# shift-in-midi.net
KiCad netlist of a schematic drawn in EAGLE
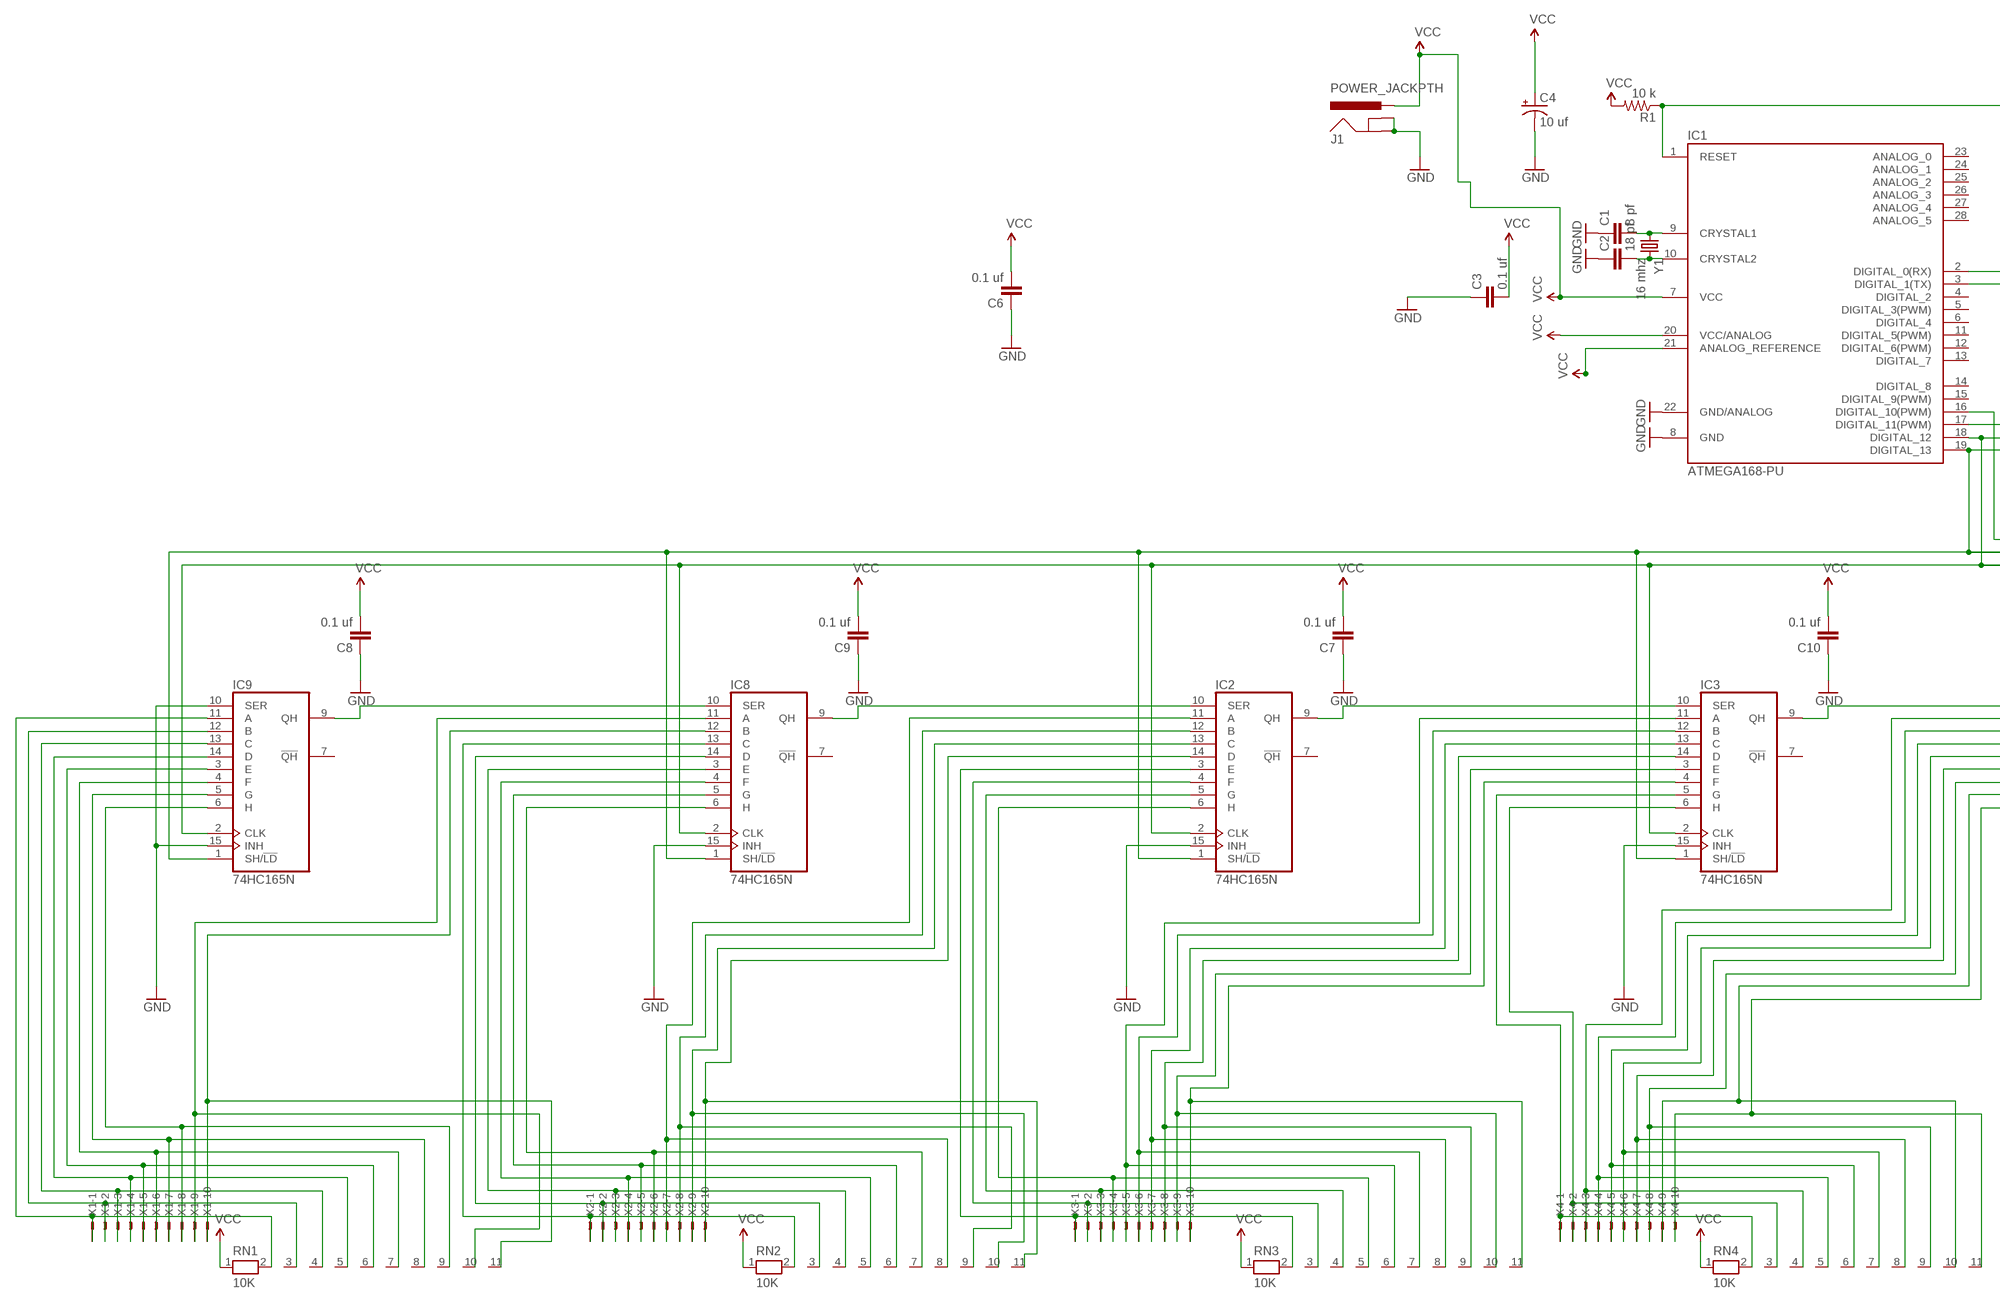
[diagram p0: schematic, sheet 1, part 1 of 2]
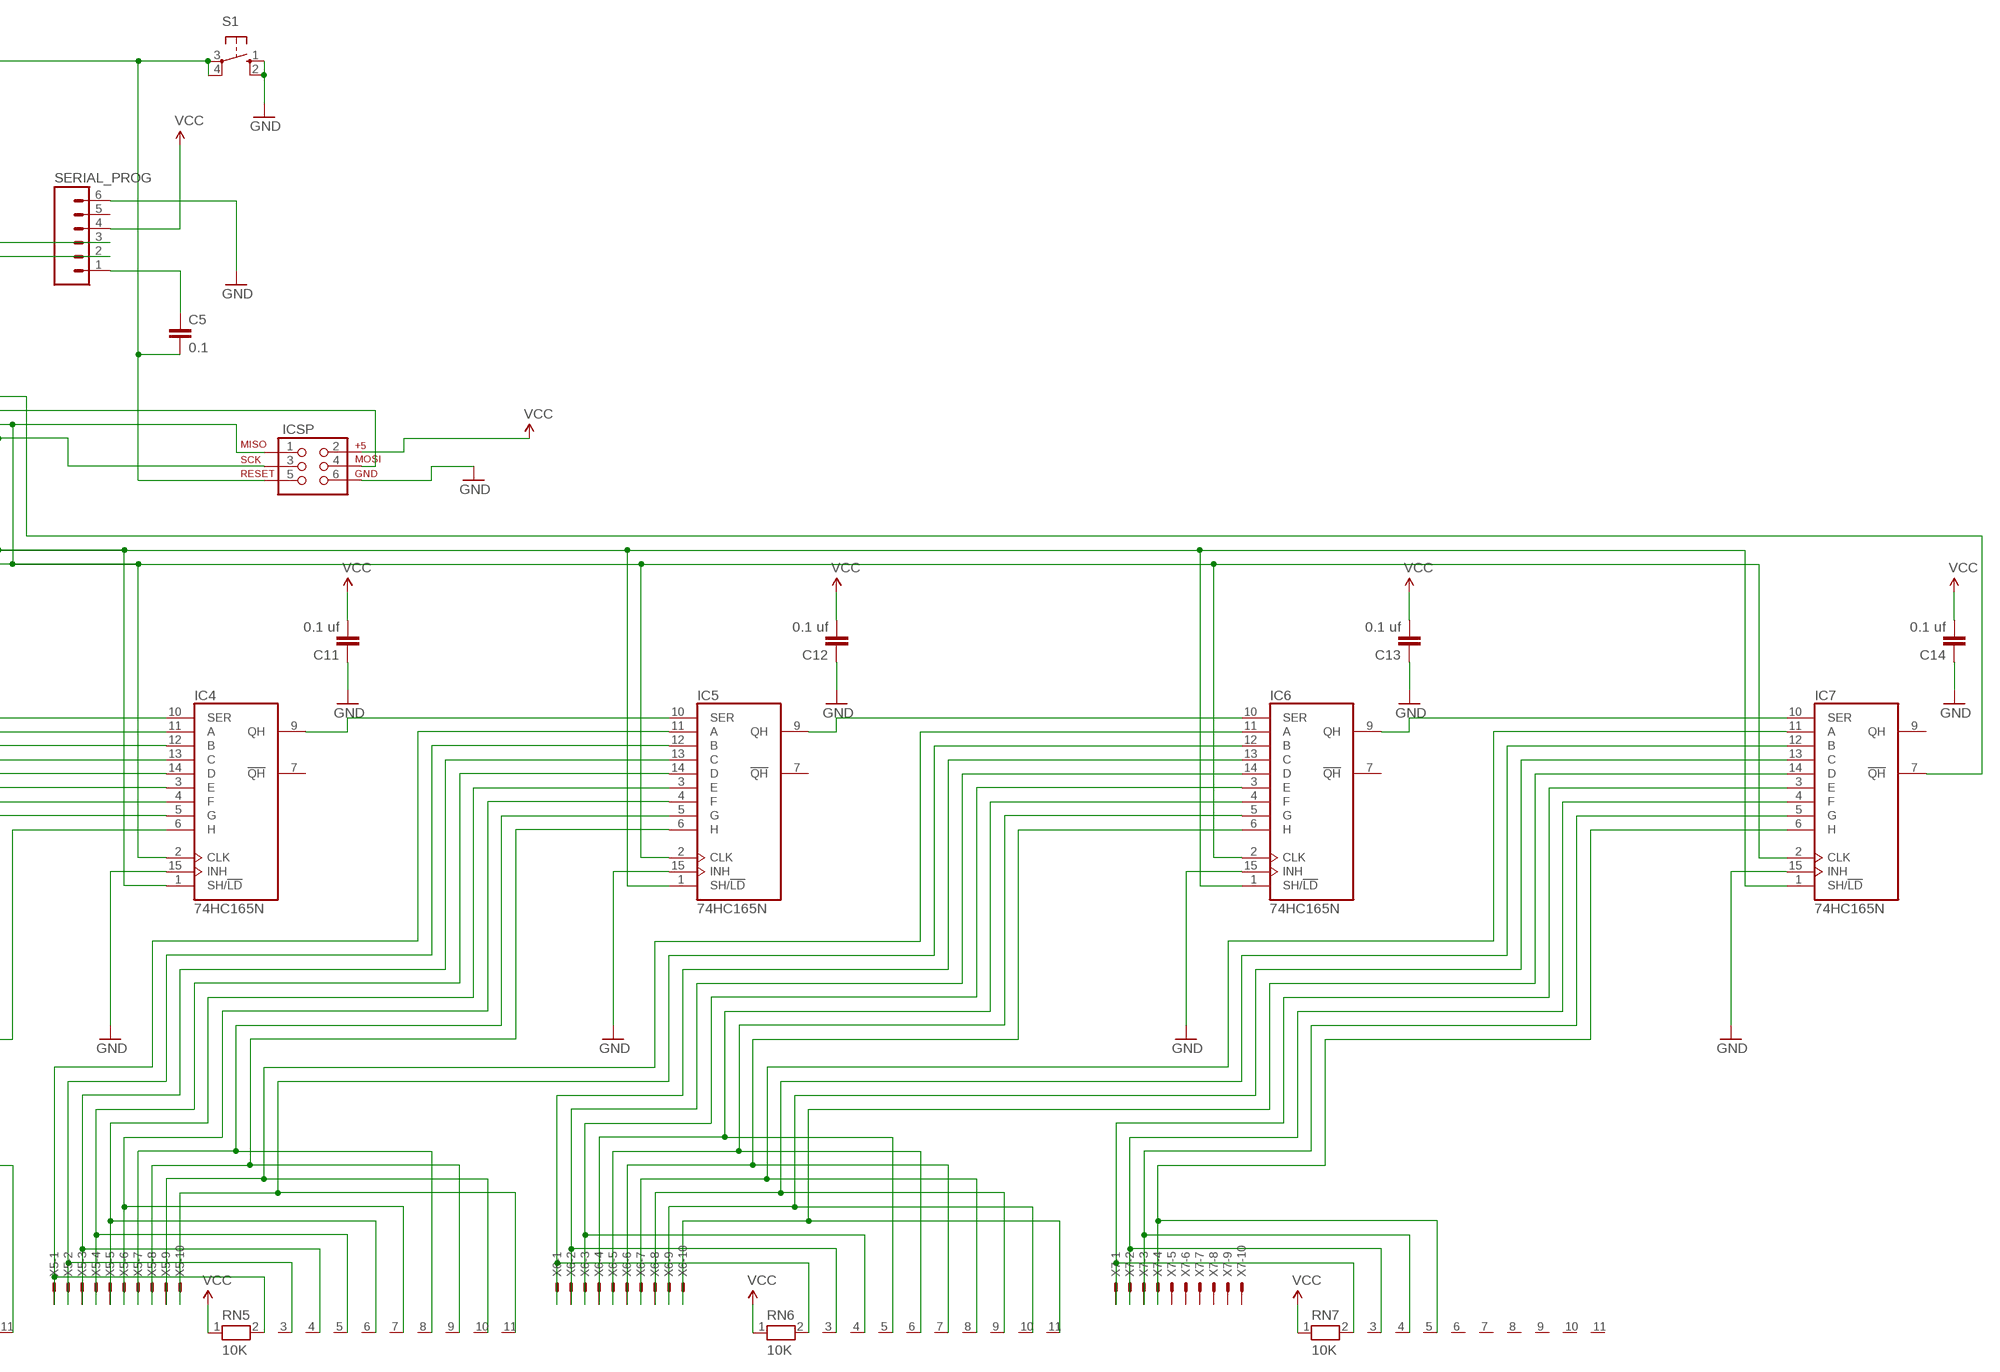
[diagram p1: schematic, sheet 1, part 2 of 2]

(export (version "E")
  (design (tool "Eeschema 10.0.6"))
  (components
    (comp (ref "C1")
      (value "8 pf")
      (footprint "eagle-import:CAP-PTH-SMALL2")
      (libsource (lib "eagle-import") (part "CAPPTH2"))
    )
    (comp (ref "C2")
      (value "18 pf")
      (footprint "eagle-import:CAP-PTH-SMALL2")
      (libsource (lib "eagle-import") (part "CAPPTH2"))
    )
    (comp (ref "C3")
      (value "0.1 uf")
      (footprint "eagle-import:CAP-PTH-SMALL2")
      (libsource (lib "eagle-import") (part "CAPPTH2"))
    )
    (comp (ref "C4")
      (value "10 uf")
      (footprint "eagle-import:CPOL-RADIAL-10UF-25V")
      (libsource (lib "eagle-import") (part "CAP_POLPTH2"))
    )
    (comp (ref "C5")
      (value "0.1")
      (footprint "eagle-import:CAP-PTH-SMALL")
      (libsource (lib "eagle-import") (part "SparkFun-Passives_CAPPTH"))
    )
    (comp (ref "C6")
      (value "0.1 uf")
      (footprint "eagle-import:CAP-PTH-SMALL2")
      (libsource (lib "eagle-import") (part "CAPPTH2"))
    )
    (comp (ref "C7")
      (value "0.1 uf")
      (footprint "eagle-import:CAP-PTH-SMALL2")
      (libsource (lib "eagle-import") (part "CAPPTH2"))
    )
    (comp (ref "C8")
      (value "0.1 uf")
      (footprint "eagle-import:CAP-PTH-SMALL2")
      (libsource (lib "eagle-import") (part "CAPPTH2"))
    )
    (comp (ref "C9")
      (value "0.1 uf")
      (footprint "eagle-import:CAP-PTH-SMALL2")
      (libsource (lib "eagle-import") (part "CAPPTH2"))
    )
    (comp (ref "C10")
      (value "0.1 uf")
      (footprint "eagle-import:CAP-PTH-SMALL2")
      (libsource (lib "eagle-import") (part "CAPPTH2"))
    )
    (comp (ref "C11")
      (value "0.1 uf")
      (footprint "eagle-import:CAP-PTH-SMALL2")
      (libsource (lib "eagle-import") (part "CAPPTH2"))
    )
    (comp (ref "C12")
      (value "0.1 uf")
      (footprint "eagle-import:CAP-PTH-SMALL2")
      (libsource (lib "eagle-import") (part "CAPPTH2"))
    )
    (comp (ref "C13")
      (value "0.1 uf")
      (footprint "eagle-import:CAP-PTH-SMALL2")
      (libsource (lib "eagle-import") (part "CAPPTH2"))
    )
    (comp (ref "C14")
      (value "0.1 uf")
      (footprint "eagle-import:CAP-PTH-SMALL2")
      (libsource (lib "eagle-import") (part "CAPPTH2"))
    )
    (comp (ref "IC1")
      (value "ATMEGA168-PU")
      (footprint "eagle-import:DIL28-3")
      (libsource (lib "eagle-import") (part "ATMEGA168-PU"))
    )
    (comp (ref "IC2")
      (value "74HC165N")
      (footprint "eagle-import:DIL16")
      (libsource (lib "eagle-import") (part "74165NHC"))
    )
    (comp (ref "IC3")
      (value "74HC165N")
      (footprint "eagle-import:DIL16")
      (libsource (lib "eagle-import") (part "74165NHC"))
    )
    (comp (ref "IC4")
      (value "74HC165N")
      (footprint "eagle-import:DIL16")
      (libsource (lib "eagle-import") (part "74165NHC"))
    )
    (comp (ref "IC5")
      (value "74HC165N")
      (footprint "eagle-import:DIL16")
      (libsource (lib "eagle-import") (part "74165NHC"))
    )
    (comp (ref "IC6")
      (value "74HC165N")
      (footprint "eagle-import:DIL16")
      (libsource (lib "eagle-import") (part "74165NHC"))
    )
    (comp (ref "IC7")
      (value "74HC165N")
      (footprint "eagle-import:DIL16")
      (libsource (lib "eagle-import") (part "74165NHC"))
    )
    (comp (ref "IC8")
      (value "74HC165N")
      (footprint "eagle-import:DIL16")
      (libsource (lib "eagle-import") (part "74165NHC"))
    )
    (comp (ref "IC9")
      (value "74HC165N")
      (footprint "eagle-import:DIL16")
      (libsource (lib "eagle-import") (part "74165NHC"))
    )
    (comp (ref "ICSP")
      (value "AVR_SPI_PRG_62X3_LOCK")
      (footprint "eagle-import:2X3_LOCK")
      (libsource (lib "eagle-import") (part "AVR_SPI_PRG_62X3_LOCK"))
    )
    (comp (ref "J1")
      (value "POWER_JACKPTH")
      (footprint "eagle-import:POWER_JACK_PTH")
      (libsource (lib "eagle-import") (part "POWER_JACKPTH"))
    )
    (comp (ref "R1")
      (value "10 k")
      (footprint "eagle-import:AXIAL-0.4")
      (libsource (lib "eagle-import") (part "RESISTORPTH-1/4W"))
    )
    (comp (ref "RN1")
      (value "10K")
      (footprint "eagle-import:RN-11")
      (libsource (lib "eagle-import") (part "RN10"))
    )
    (comp (ref "RN2")
      (value "10K")
      (footprint "eagle-import:RN-11")
      (fields (field (name "OC_FARNELL") "unknown") (field (name "OC_NEWARK") "unknown"))
      (libsource (lib "eagle-import") (part "RN10"))
    )
    (comp (ref "RN3")
      (value "10K")
      (footprint "eagle-import:RN-11")
      (fields (field (name "OC_FARNELL") "unknown") (field (name "OC_NEWARK") "unknown"))
      (libsource (lib "eagle-import") (part "RN10"))
    )
    (comp (ref "RN4")
      (value "10K")
      (footprint "eagle-import:RN-11")
      (fields (field (name "OC_FARNELL") "unknown") (field (name "OC_NEWARK") "unknown"))
      (libsource (lib "eagle-import") (part "RN10"))
    )
    (comp (ref "RN5")
      (value "10K")
      (footprint "eagle-import:RN-11")
      (fields (field (name "OC_FARNELL") "unknown") (field (name "OC_NEWARK") "unknown"))
      (libsource (lib "eagle-import") (part "RN10"))
    )
    (comp (ref "RN6")
      (value "10K")
      (footprint "eagle-import:RN-11")
      (fields (field (name "OC_FARNELL") "unknown") (field (name "OC_NEWARK") "unknown"))
      (libsource (lib "eagle-import") (part "RN10"))
    )
    (comp (ref "RN7")
      (value "10K")
      (footprint "eagle-import:RN-11")
      (fields (field (name "OC_FARNELL") "unknown") (field (name "OC_NEWARK") "unknown"))
      (libsource (lib "eagle-import") (part "RN10"))
    )
    (comp (ref "S1")
      (value "10-XX")
      (footprint "eagle-import:B3F-10XX")
      (fields (field (name "MPN") "B3F-1000"))
      (libsource (lib "eagle-import") (part "10-XX"))
    )
    (comp (ref "SERIAL_PROG")
      (value "M06LONGPADS")
      (footprint "eagle-import:1X06_LONGPADS")
      (libsource (lib "eagle-import") (part "M06LONGPADS"))
    )
    (comp (ref "X1")
      (value "KK-156-10")
      (footprint "eagle-import:KK-156-10")
      (libsource (lib "eagle-import") (part "KK-156-10"))
    )
    (comp (ref "X2")
      (value "KK-156-10")
      (footprint "eagle-import:KK-156-10")
      (libsource (lib "eagle-import") (part "KK-156-10"))
    )
    (comp (ref "X3")
      (value "KK-156-10")
      (footprint "eagle-import:KK-156-10")
      (libsource (lib "eagle-import") (part "KK-156-10"))
    )
    (comp (ref "X4")
      (value "KK-156-10")
      (footprint "eagle-import:KK-156-10")
      (libsource (lib "eagle-import") (part "KK-156-10"))
    )
    (comp (ref "X5")
      (value "KK-156-10")
      (footprint "eagle-import:KK-156-10")
      (libsource (lib "eagle-import") (part "KK-156-10"))
    )
    (comp (ref "X6")
      (value "KK-156-10")
      (footprint "eagle-import:KK-156-10")
      (libsource (lib "eagle-import") (part "KK-156-10"))
    )
    (comp (ref "X7")
      (value "KK-156-10")
      (footprint "eagle-import:KK-156-10")
      (libsource (lib "eagle-import") (part "KK-156-10"))
    )
    (comp (ref "Y1")
      (value "16 mhz")
      (footprint "eagle-import:HC49US")
      (libsource (lib "eagle-import") (part "CRYSTALHC49US"))
    )
  )
  (nets
    (net (code "1") (name "GND") (class "Default")
      (node (ref "C1") (pin "1") (pinfunction "1_1") (pintype "passive"))
      (node (ref "C10") (pin "1") (pinfunction "1_1") (pintype "passive"))
      (node (ref "C11") (pin "1") (pinfunction "1_1") (pintype "passive"))
      (node (ref "C12") (pin "1") (pinfunction "1_1") (pintype "passive"))
      (node (ref "C13") (pin "1") (pinfunction "1_1") (pintype "passive"))
      (node (ref "C14") (pin "1") (pinfunction "1_1") (pintype "passive"))
      (node (ref "C2") (pin "1") (pinfunction "1_1") (pintype "passive"))
      (node (ref "C3") (pin "1") (pinfunction "1_1") (pintype "passive"))
      (node (ref "C4") (pin "2") (pinfunction "-_2") (pintype "passive"))
      (node (ref "C6") (pin "1") (pinfunction "1_1") (pintype "passive"))
      (node (ref "C7") (pin "1") (pinfunction "1_1") (pintype "passive"))
      (node (ref "C8") (pin "1") (pinfunction "1_1") (pintype "passive"))
      (node (ref "C9") (pin "1") (pinfunction "1_1") (pintype "passive"))
      (node (ref "IC1") (pin "22") (pinfunction "GND/ANALOG_22") (pintype "power_in"))
      (node (ref "IC1") (pin "8") (pinfunction "GND_8") (pintype "power_in"))
      (node (ref "IC2") (pin "15") (pinfunction "INH_15") (pintype "input"))
      (node (ref "IC3") (pin "15") (pinfunction "INH_15") (pintype "input"))
      (node (ref "IC4") (pin "15") (pinfunction "INH_15") (pintype "input"))
      (node (ref "IC5") (pin "15") (pinfunction "INH_15") (pintype "input"))
      (node (ref "IC6") (pin "15") (pinfunction "INH_15") (pintype "input"))
      (node (ref "IC7") (pin "15") (pinfunction "INH_15") (pintype "input"))
      (node (ref "IC8") (pin "15") (pinfunction "INH_15") (pintype "input"))
      (node (ref "IC9") (pin "10") (pinfunction "SER_10") (pintype "input"))
      (node (ref "IC9") (pin "15") (pinfunction "INH_15") (pintype "input"))
      (node (ref "ICSP") (pin "6") (pinfunction "6_6") (pintype "passive"))
      (node (ref "J1") (pin "GND") (pinfunction "GND_GND") (pintype "bidirectional"))
      (node (ref "J1") (pin "GNDBREAK") (pinfunction "GNDBREAK_GNDBREAK") (pintype "bidirectional"))
      (node (ref "S1") (pin "1") (pinfunction "S_1") (pintype "passive"))
      (node (ref "S1") (pin "2") (pinfunction "S1_2") (pintype "passive"))
      (node (ref "SERIAL_PROG") (pin "6") (pinfunction "6_6") (pintype "passive"))
    )
    (net (code "2") (name "Net-(C5-Pad1)") (class "Default")
      (node (ref "C5") (pin "1") (pinfunction "1_1") (pintype "passive"))
      (node (ref "SERIAL_PROG") (pin "1") (pinfunction "1_1") (pintype "passive"))
    )
    (net (code "3") (name "Net-(IC1-CRYSTAL1)") (class "Default")
      (node (ref "C1") (pin "2") (pinfunction "2_2") (pintype "passive"))
      (node (ref "IC1") (pin "9") (pinfunction "CRYSTAL1_9") (pintype "bidirectional"))
      (node (ref "Y1") (pin "1") (pinfunction "1_1") (pintype "passive"))
    )
    (net (code "4") (name "Net-(IC1-CRYSTAL2)") (class "Default")
      (node (ref "C2") (pin "2") (pinfunction "2_2") (pintype "passive"))
      (node (ref "IC1") (pin "10") (pinfunction "CRYSTAL2_10") (pintype "bidirectional"))
      (node (ref "Y1") (pin "2") (pinfunction "2_2") (pintype "passive"))
    )
    (net (code "5") (name "Net-(IC1-DIGITAL_0(RX))") (class "Default")
      (node (ref "IC1") (pin "2") (pinfunction "DIGITAL_0(RX)_2") (pintype "bidirectional"))
      (node (ref "SERIAL_PROG") (pin "3") (pinfunction "3_3") (pintype "passive"))
    )
    (net (code "6") (name "Net-(IC1-DIGITAL_1(TX))") (class "Default")
      (node (ref "IC1") (pin "3") (pinfunction "DIGITAL_1(TX)_3") (pintype "bidirectional"))
      (node (ref "SERIAL_PROG") (pin "2") (pinfunction "2_2") (pintype "passive"))
    )
    (net (code "7") (name "Net-(IC1-DIGITAL_10(PWM))") (class "Default")
      (node (ref "IC1") (pin "16") (pinfunction "DIGITAL_10(PWM)_16") (pintype "bidirectional"))
      (node (ref "IC7") (pin "7") (pinfunction "~{QH}_7") (pintype "output"))
    )
    (net (code "8") (name "Net-(IC1-DIGITAL_11(PWM))") (class "Default")
      (node (ref "IC1") (pin "17") (pinfunction "DIGITAL_11(PWM)_17") (pintype "bidirectional"))
      (node (ref "ICSP") (pin "4") (pinfunction "4_4") (pintype "passive"))
    )
    (net (code "9") (name "Net-(IC1-DIGITAL_12)") (class "Default")
      (node (ref "IC1") (pin "18") (pinfunction "DIGITAL_12_18") (pintype "bidirectional"))
      (node (ref "IC2") (pin "2") (pinfunction "CLK_2") (pintype "input"))
      (node (ref "IC3") (pin "2") (pinfunction "CLK_2") (pintype "input"))
      (node (ref "IC4") (pin "2") (pinfunction "CLK_2") (pintype "input"))
      (node (ref "IC5") (pin "2") (pinfunction "CLK_2") (pintype "input"))
      (node (ref "IC6") (pin "2") (pinfunction "CLK_2") (pintype "input"))
      (node (ref "IC7") (pin "2") (pinfunction "CLK_2") (pintype "input"))
      (node (ref "IC8") (pin "2") (pinfunction "CLK_2") (pintype "input"))
      (node (ref "IC9") (pin "2") (pinfunction "CLK_2") (pintype "input"))
      (node (ref "ICSP") (pin "1") (pinfunction "1_1") (pintype "passive"))
    )
    (net (code "10") (name "Net-(IC1-DIGITAL_13)") (class "Default")
      (node (ref "IC1") (pin "19") (pinfunction "DIGITAL_13_19") (pintype "bidirectional"))
      (node (ref "IC2") (pin "1") (pinfunction "SH/~{LD}_1") (pintype "input"))
      (node (ref "IC3") (pin "1") (pinfunction "SH/~{LD}_1") (pintype "input"))
      (node (ref "IC4") (pin "1") (pinfunction "SH/~{LD}_1") (pintype "input"))
      (node (ref "IC5") (pin "1") (pinfunction "SH/~{LD}_1") (pintype "input"))
      (node (ref "IC6") (pin "1") (pinfunction "SH/~{LD}_1") (pintype "input"))
      (node (ref "IC7") (pin "1") (pinfunction "SH/~{LD}_1") (pintype "input"))
      (node (ref "IC8") (pin "1") (pinfunction "SH/~{LD}_1") (pintype "input"))
      (node (ref "IC9") (pin "1") (pinfunction "SH/~{LD}_1") (pintype "input"))
      (node (ref "ICSP") (pin "3") (pinfunction "3_3") (pintype "passive"))
    )
    (net (code "11") (name "Net-(IC1-RESET)") (class "Default")
      (node (ref "C5") (pin "2") (pinfunction "2_2") (pintype "passive"))
      (node (ref "IC1") (pin "1") (pinfunction "RESET_1") (pintype "bidirectional"))
      (node (ref "ICSP") (pin "5") (pinfunction "5_5") (pintype "passive"))
      (node (ref "R1") (pin "P$1") (pinfunction "1_P$1") (pintype "passive"))
      (node (ref "S1") (pin "3") (pinfunction "P_3") (pintype "passive"))
      (node (ref "S1") (pin "4") (pinfunction "P1_4") (pintype "passive"))
    )
    (net (code "12") (name "Net-(IC2A-A)") (class "Default")
      (node (ref "IC2") (pin "11") (pinfunction "A_11") (pintype "input"))
      (node (ref "RN2") (pin "8") (pinfunction "8_8") (pintype "passive"))
      (node (ref "X2") (pin "7") (pinfunction "S_7") (pintype "passive"))
    )
    (net (code "13") (name "Net-(IC2A-B)") (class "Default")
      (node (ref "IC2") (pin "12") (pinfunction "B_12") (pintype "input"))
      (node (ref "RN2") (pin "9") (pinfunction "9_9") (pintype "passive"))
      (node (ref "X2") (pin "8") (pinfunction "S_8") (pintype "passive"))
    )
    (net (code "14") (name "Net-(IC2A-C)") (class "Default")
      (node (ref "IC2") (pin "13") (pinfunction "C_13") (pintype "input"))
      (node (ref "RN2") (pin "10") (pinfunction "10_10") (pintype "passive"))
      (node (ref "X2") (pin "9") (pinfunction "S_9") (pintype "passive"))
    )
    (net (code "15") (name "Net-(IC2A-D)") (class "Default")
      (node (ref "IC2") (pin "14") (pinfunction "D_14") (pintype "input"))
      (node (ref "RN2") (pin "11") (pinfunction "11_11") (pintype "passive"))
      (node (ref "X2") (pin "10") (pinfunction "S_10") (pintype "passive"))
    )
    (net (code "16") (name "Net-(IC2A-E)") (class "Default")
      (node (ref "IC2") (pin "3") (pinfunction "E_3") (pintype "input"))
      (node (ref "RN3") (pin "2") (pinfunction "2_2") (pintype "passive"))
      (node (ref "X3") (pin "1") (pinfunction "S_1") (pintype "passive"))
    )
    (net (code "17") (name "Net-(IC2A-F)") (class "Default")
      (node (ref "IC2") (pin "4") (pinfunction "F_4") (pintype "input"))
      (node (ref "RN3") (pin "3") (pinfunction "3_3") (pintype "passive"))
      (node (ref "X3") (pin "2") (pinfunction "S_2") (pintype "passive"))
    )
    (net (code "18") (name "Net-(IC2A-G)") (class "Default")
      (node (ref "IC2") (pin "5") (pinfunction "G_5") (pintype "input"))
      (node (ref "RN3") (pin "4") (pinfunction "4_4") (pintype "passive"))
      (node (ref "X3") (pin "3") (pinfunction "S_3") (pintype "passive"))
    )
    (net (code "19") (name "Net-(IC2A-H)") (class "Default")
      (node (ref "IC2") (pin "6") (pinfunction "H_6") (pintype "input"))
      (node (ref "RN3") (pin "5") (pinfunction "5_5") (pintype "passive"))
      (node (ref "X3") (pin "4") (pinfunction "S_4") (pintype "passive"))
    )
    (net (code "20") (name "Net-(IC2A-QH)") (class "Default")
      (node (ref "IC2") (pin "9") (pinfunction "QH_9") (pintype "output"))
      (node (ref "IC3") (pin "10") (pinfunction "SER_10") (pintype "input"))
    )
    (net (code "21") (name "Net-(IC2A-SER)") (class "Default")
      (node (ref "IC2") (pin "10") (pinfunction "SER_10") (pintype "input"))
      (node (ref "IC8") (pin "9") (pinfunction "QH_9") (pintype "output"))
    )
    (net (code "22") (name "Net-(IC3A-A)") (class "Default")
      (node (ref "IC3") (pin "11") (pinfunction "A_11") (pintype "input"))
      (node (ref "RN3") (pin "6") (pinfunction "6_6") (pintype "passive"))
      (node (ref "X3") (pin "5") (pinfunction "S_5") (pintype "passive"))
    )
    (net (code "23") (name "Net-(IC3A-B)") (class "Default")
      (node (ref "IC3") (pin "12") (pinfunction "B_12") (pintype "input"))
      (node (ref "RN3") (pin "7") (pinfunction "7_7") (pintype "passive"))
      (node (ref "X3") (pin "6") (pinfunction "S_6") (pintype "passive"))
    )
    (net (code "24") (name "Net-(IC3A-C)") (class "Default")
      (node (ref "IC3") (pin "13") (pinfunction "C_13") (pintype "input"))
      (node (ref "RN3") (pin "8") (pinfunction "8_8") (pintype "passive"))
      (node (ref "X3") (pin "7") (pinfunction "S_7") (pintype "passive"))
    )
    (net (code "25") (name "Net-(IC3A-D)") (class "Default")
      (node (ref "IC3") (pin "14") (pinfunction "D_14") (pintype "input"))
      (node (ref "RN3") (pin "9") (pinfunction "9_9") (pintype "passive"))
      (node (ref "X3") (pin "8") (pinfunction "S_8") (pintype "passive"))
    )
    (net (code "26") (name "Net-(IC3A-E)") (class "Default")
      (node (ref "IC3") (pin "3") (pinfunction "E_3") (pintype "input"))
      (node (ref "RN3") (pin "10") (pinfunction "10_10") (pintype "passive"))
      (node (ref "X3") (pin "9") (pinfunction "S_9") (pintype "passive"))
    )
    (net (code "27") (name "Net-(IC3A-F)") (class "Default")
      (node (ref "IC3") (pin "4") (pinfunction "F_4") (pintype "input"))
      (node (ref "RN3") (pin "11") (pinfunction "11_11") (pintype "passive"))
      (node (ref "X3") (pin "10") (pinfunction "S_10") (pintype "passive"))
    )
    (net (code "28") (name "Net-(IC3A-G)") (class "Default")
      (node (ref "IC3") (pin "5") (pinfunction "G_5") (pintype "input"))
      (node (ref "RN4") (pin "2") (pinfunction "2_2") (pintype "passive"))
      (node (ref "X4") (pin "1") (pinfunction "S_1") (pintype "passive"))
    )
    (net (code "29") (name "Net-(IC3A-H)") (class "Default")
      (node (ref "IC3") (pin "6") (pinfunction "H_6") (pintype "input"))
      (node (ref "RN4") (pin "3") (pinfunction "3_3") (pintype "passive"))
      (node (ref "X4") (pin "2") (pinfunction "S_2") (pintype "passive"))
    )
    (net (code "30") (name "Net-(IC3A-QH)") (class "Default")
      (node (ref "IC3") (pin "9") (pinfunction "QH_9") (pintype "output"))
      (node (ref "IC4") (pin "10") (pinfunction "SER_10") (pintype "input"))
    )
    (net (code "31") (name "Net-(IC4A-A)") (class "Default")
      (node (ref "IC4") (pin "11") (pinfunction "A_11") (pintype "input"))
      (node (ref "RN4") (pin "4") (pinfunction "4_4") (pintype "passive"))
      (node (ref "X4") (pin "3") (pinfunction "S_3") (pintype "passive"))
    )
    (net (code "32") (name "Net-(IC4A-B)") (class "Default")
      (node (ref "IC4") (pin "12") (pinfunction "B_12") (pintype "input"))
      (node (ref "RN4") (pin "5") (pinfunction "5_5") (pintype "passive"))
      (node (ref "X4") (pin "4") (pinfunction "S_4") (pintype "passive"))
    )
    (net (code "33") (name "Net-(IC4A-C)") (class "Default")
      (node (ref "IC4") (pin "13") (pinfunction "C_13") (pintype "input"))
      (node (ref "RN4") (pin "6") (pinfunction "6_6") (pintype "passive"))
      (node (ref "X4") (pin "5") (pinfunction "S_5") (pintype "passive"))
    )
    (net (code "34") (name "Net-(IC4A-D)") (class "Default")
      (node (ref "IC4") (pin "14") (pinfunction "D_14") (pintype "input"))
      (node (ref "RN4") (pin "7") (pinfunction "7_7") (pintype "passive"))
      (node (ref "X4") (pin "6") (pinfunction "S_6") (pintype "passive"))
    )
    (net (code "35") (name "Net-(IC4A-E)") (class "Default")
      (node (ref "IC4") (pin "3") (pinfunction "E_3") (pintype "input"))
      (node (ref "RN4") (pin "8") (pinfunction "8_8") (pintype "passive"))
      (node (ref "X4") (pin "7") (pinfunction "S_7") (pintype "passive"))
    )
    (net (code "36") (name "Net-(IC4A-F)") (class "Default")
      (node (ref "IC4") (pin "4") (pinfunction "F_4") (pintype "input"))
      (node (ref "RN4") (pin "9") (pinfunction "9_9") (pintype "passive"))
      (node (ref "X4") (pin "8") (pinfunction "S_8") (pintype "passive"))
    )
    (net (code "37") (name "Net-(IC4A-G)") (class "Default")
      (node (ref "IC4") (pin "5") (pinfunction "G_5") (pintype "input"))
      (node (ref "RN4") (pin "10") (pinfunction "10_10") (pintype "passive"))
      (node (ref "X4") (pin "9") (pinfunction "S_9") (pintype "passive"))
    )
    (net (code "38") (name "Net-(IC4A-H)") (class "Default")
      (node (ref "IC4") (pin "6") (pinfunction "H_6") (pintype "input"))
      (node (ref "RN4") (pin "11") (pinfunction "11_11") (pintype "passive"))
      (node (ref "X4") (pin "10") (pinfunction "S_10") (pintype "passive"))
    )
    (net (code "39") (name "Net-(IC4A-QH)") (class "Default")
      (node (ref "IC4") (pin "9") (pinfunction "QH_9") (pintype "output"))
      (node (ref "IC5") (pin "10") (pinfunction "SER_10") (pintype "input"))
    )
    (net (code "40") (name "Net-(IC5A-A)") (class "Default")
      (node (ref "IC5") (pin "11") (pinfunction "A_11") (pintype "input"))
      (node (ref "RN5") (pin "2") (pinfunction "2_2") (pintype "passive"))
      (node (ref "X5") (pin "1") (pinfunction "S_1") (pintype "passive"))
    )
    (net (code "41") (name "Net-(IC5A-B)") (class "Default")
      (node (ref "IC5") (pin "12") (pinfunction "B_12") (pintype "input"))
      (node (ref "RN5") (pin "3") (pinfunction "3_3") (pintype "passive"))
      (node (ref "X5") (pin "2") (pinfunction "S_2") (pintype "passive"))
    )
    (net (code "42") (name "Net-(IC5A-C)") (class "Default")
      (node (ref "IC5") (pin "13") (pinfunction "C_13") (pintype "input"))
      (node (ref "RN5") (pin "4") (pinfunction "4_4") (pintype "passive"))
      (node (ref "X5") (pin "3") (pinfunction "S_3") (pintype "passive"))
    )
    (net (code "43") (name "Net-(IC5A-D)") (class "Default")
      (node (ref "IC5") (pin "14") (pinfunction "D_14") (pintype "input"))
      (node (ref "RN5") (pin "5") (pinfunction "5_5") (pintype "passive"))
      (node (ref "X5") (pin "4") (pinfunction "S_4") (pintype "passive"))
    )
    (net (code "44") (name "Net-(IC5A-E)") (class "Default")
      (node (ref "IC5") (pin "3") (pinfunction "E_3") (pintype "input"))
      (node (ref "RN5") (pin "6") (pinfunction "6_6") (pintype "passive"))
      (node (ref "X5") (pin "5") (pinfunction "S_5") (pintype "passive"))
    )
    (net (code "45") (name "Net-(IC5A-F)") (class "Default")
      (node (ref "IC5") (pin "4") (pinfunction "F_4") (pintype "input"))
      (node (ref "RN5") (pin "7") (pinfunction "7_7") (pintype "passive"))
      (node (ref "X5") (pin "6") (pinfunction "S_6") (pintype "passive"))
    )
    (net (code "46") (name "Net-(IC5A-G)") (class "Default")
      (node (ref "IC5") (pin "5") (pinfunction "G_5") (pintype "input"))
      (node (ref "RN5") (pin "8") (pinfunction "8_8") (pintype "passive"))
      (node (ref "X5") (pin "7") (pinfunction "S_7") (pintype "passive"))
    )
    (net (code "47") (name "Net-(IC5A-H)") (class "Default")
      (node (ref "IC5") (pin "6") (pinfunction "H_6") (pintype "input"))
      (node (ref "RN5") (pin "9") (pinfunction "9_9") (pintype "passive"))
      (node (ref "X5") (pin "8") (pinfunction "S_8") (pintype "passive"))
    )
    (net (code "48") (name "Net-(IC5A-QH)") (class "Default")
      (node (ref "IC5") (pin "9") (pinfunction "QH_9") (pintype "output"))
      (node (ref "IC6") (pin "10") (pinfunction "SER_10") (pintype "input"))
    )
    (net (code "49") (name "Net-(IC6A-A)") (class "Default")
      (node (ref "IC6") (pin "11") (pinfunction "A_11") (pintype "input"))
      (node (ref "RN5") (pin "10") (pinfunction "10_10") (pintype "passive"))
      (node (ref "X5") (pin "9") (pinfunction "S_9") (pintype "passive"))
    )
    (net (code "50") (name "Net-(IC6A-B)") (class "Default")
      (node (ref "IC6") (pin "12") (pinfunction "B_12") (pintype "input"))
      (node (ref "RN5") (pin "11") (pinfunction "11_11") (pintype "passive"))
      (node (ref "X5") (pin "10") (pinfunction "S_10") (pintype "passive"))
    )
    (net (code "51") (name "Net-(IC6A-C)") (class "Default")
      (node (ref "IC6") (pin "13") (pinfunction "C_13") (pintype "input"))
      (node (ref "RN6") (pin "2") (pinfunction "2_2") (pintype "passive"))
      (node (ref "X6") (pin "1") (pinfunction "S_1") (pintype "passive"))
    )
    (net (code "52") (name "Net-(IC6A-D)") (class "Default")
      (node (ref "IC6") (pin "14") (pinfunction "D_14") (pintype "input"))
      (node (ref "RN6") (pin "3") (pinfunction "3_3") (pintype "passive"))
      (node (ref "X6") (pin "2") (pinfunction "S_2") (pintype "passive"))
    )
    (net (code "53") (name "Net-(IC6A-E)") (class "Default")
      (node (ref "IC6") (pin "3") (pinfunction "E_3") (pintype "input"))
      (node (ref "RN6") (pin "4") (pinfunction "4_4") (pintype "passive"))
      (node (ref "X6") (pin "3") (pinfunction "S_3") (pintype "passive"))
    )
    (net (code "54") (name "Net-(IC6A-F)") (class "Default")
      (node (ref "IC6") (pin "4") (pinfunction "F_4") (pintype "input"))
      (node (ref "RN6") (pin "5") (pinfunction "5_5") (pintype "passive"))
      (node (ref "X6") (pin "4") (pinfunction "S_4") (pintype "passive"))
    )
    (net (code "55") (name "Net-(IC6A-G)") (class "Default")
      (node (ref "IC6") (pin "5") (pinfunction "G_5") (pintype "input"))
      (node (ref "RN6") (pin "6") (pinfunction "6_6") (pintype "passive"))
      (node (ref "X6") (pin "5") (pinfunction "S_5") (pintype "passive"))
    )
    (net (code "56") (name "Net-(IC6A-H)") (class "Default")
      (node (ref "IC6") (pin "6") (pinfunction "H_6") (pintype "input"))
      (node (ref "RN6") (pin "7") (pinfunction "7_7") (pintype "passive"))
      (node (ref "X6") (pin "6") (pinfunction "S_6") (pintype "passive"))
    )
    (net (code "57") (name "Net-(IC6A-QH)") (class "Default")
      (node (ref "IC6") (pin "9") (pinfunction "QH_9") (pintype "output"))
      (node (ref "IC7") (pin "10") (pinfunction "SER_10") (pintype "input"))
    )
    (net (code "58") (name "Net-(IC7A-A)") (class "Default")
      (node (ref "IC7") (pin "11") (pinfunction "A_11") (pintype "input"))
      (node (ref "RN6") (pin "8") (pinfunction "8_8") (pintype "passive"))
      (node (ref "X6") (pin "7") (pinfunction "S_7") (pintype "passive"))
    )
    (net (code "59") (name "Net-(IC7A-B)") (class "Default")
      (node (ref "IC7") (pin "12") (pinfunction "B_12") (pintype "input"))
      (node (ref "RN6") (pin "9") (pinfunction "9_9") (pintype "passive"))
      (node (ref "X6") (pin "8") (pinfunction "S_8") (pintype "passive"))
    )
    (net (code "60") (name "Net-(IC7A-C)") (class "Default")
      (node (ref "IC7") (pin "13") (pinfunction "C_13") (pintype "input"))
      (node (ref "RN6") (pin "10") (pinfunction "10_10") (pintype "passive"))
      (node (ref "X6") (pin "9") (pinfunction "S_9") (pintype "passive"))
    )
    (net (code "61") (name "Net-(IC7A-D)") (class "Default")
      (node (ref "IC7") (pin "14") (pinfunction "D_14") (pintype "input"))
      (node (ref "RN6") (pin "11") (pinfunction "11_11") (pintype "passive"))
      (node (ref "X6") (pin "10") (pinfunction "S_10") (pintype "passive"))
    )
    (net (code "62") (name "Net-(IC7A-E)") (class "Default")
      (node (ref "IC7") (pin "3") (pinfunction "E_3") (pintype "input"))
      (node (ref "RN7") (pin "2") (pinfunction "2_2") (pintype "passive"))
      (node (ref "X7") (pin "1") (pinfunction "S_1") (pintype "passive"))
    )
    (net (code "63") (name "Net-(IC7A-F)") (class "Default")
      (node (ref "IC7") (pin "4") (pinfunction "F_4") (pintype "input"))
      (node (ref "RN7") (pin "3") (pinfunction "3_3") (pintype "passive"))
      (node (ref "X7") (pin "2") (pinfunction "S_2") (pintype "passive"))
    )
    (net (code "64") (name "Net-(IC7A-G)") (class "Default")
      (node (ref "IC7") (pin "5") (pinfunction "G_5") (pintype "input"))
      (node (ref "RN7") (pin "4") (pinfunction "4_4") (pintype "passive"))
      (node (ref "X7") (pin "3") (pinfunction "S_3") (pintype "passive"))
    )
    (net (code "65") (name "Net-(IC7A-H)") (class "Default")
      (node (ref "IC7") (pin "6") (pinfunction "H_6") (pintype "input"))
      (node (ref "RN7") (pin "5") (pinfunction "5_5") (pintype "passive"))
      (node (ref "X7") (pin "4") (pinfunction "S_4") (pintype "passive"))
    )
    (net (code "66") (name "Net-(IC8A-A)") (class "Default")
      (node (ref "IC8") (pin "11") (pinfunction "A_11") (pintype "input"))
      (node (ref "RN1") (pin "10") (pinfunction "10_10") (pintype "passive"))
      (node (ref "X1") (pin "9") (pinfunction "S_9") (pintype "passive"))
    )
    (net (code "67") (name "Net-(IC8A-B)") (class "Default")
      (node (ref "IC8") (pin "12") (pinfunction "B_12") (pintype "input"))
      (node (ref "RN1") (pin "11") (pinfunction "11_11") (pintype "passive"))
      (node (ref "X1") (pin "10") (pinfunction "S_10") (pintype "passive"))
    )
    (net (code "68") (name "Net-(IC8A-C)") (class "Default")
      (node (ref "IC8") (pin "13") (pinfunction "C_13") (pintype "input"))
      (node (ref "RN2") (pin "2") (pinfunction "2_2") (pintype "passive"))
      (node (ref "X2") (pin "1") (pinfunction "S_1") (pintype "passive"))
    )
    (net (code "69") (name "Net-(IC8A-D)") (class "Default")
      (node (ref "IC8") (pin "14") (pinfunction "D_14") (pintype "input"))
      (node (ref "RN2") (pin "3") (pinfunction "3_3") (pintype "passive"))
      (node (ref "X2") (pin "2") (pinfunction "S_2") (pintype "passive"))
    )
    (net (code "70") (name "Net-(IC8A-E)") (class "Default")
      (node (ref "IC8") (pin "3") (pinfunction "E_3") (pintype "input"))
      (node (ref "RN2") (pin "4") (pinfunction "4_4") (pintype "passive"))
      (node (ref "X2") (pin "3") (pinfunction "S_3") (pintype "passive"))
    )
    (net (code "71") (name "Net-(IC8A-F)") (class "Default")
      (node (ref "IC8") (pin "4") (pinfunction "F_4") (pintype "input"))
      (node (ref "RN2") (pin "5") (pinfunction "5_5") (pintype "passive"))
      (node (ref "X2") (pin "4") (pinfunction "S_4") (pintype "passive"))
    )
    (net (code "72") (name "Net-(IC8A-G)") (class "Default")
      (node (ref "IC8") (pin "5") (pinfunction "G_5") (pintype "input"))
      (node (ref "RN2") (pin "6") (pinfunction "6_6") (pintype "passive"))
      (node (ref "X2") (pin "5") (pinfunction "S_5") (pintype "passive"))
    )
    (net (code "73") (name "Net-(IC8A-H)") (class "Default")
      (node (ref "IC8") (pin "6") (pinfunction "H_6") (pintype "input"))
      (node (ref "RN2") (pin "7") (pinfunction "7_7") (pintype "passive"))
      (node (ref "X2") (pin "6") (pinfunction "S_6") (pintype "passive"))
    )
    (net (code "74") (name "Net-(IC8A-SER)") (class "Default")
      (node (ref "IC8") (pin "10") (pinfunction "SER_10") (pintype "input"))
      (node (ref "IC9") (pin "9") (pinfunction "QH_9") (pintype "output"))
    )
    (net (code "75") (name "Net-(IC9A-A)") (class "Default")
      (node (ref "IC9") (pin "11") (pinfunction "A_11") (pintype "input"))
      (node (ref "RN1") (pin "2") (pinfunction "2_2") (pintype "passive"))
      (node (ref "X1") (pin "1") (pinfunction "S_1") (pintype "passive"))
    )
    (net (code "76") (name "Net-(IC9A-B)") (class "Default")
      (node (ref "IC9") (pin "12") (pinfunction "B_12") (pintype "input"))
      (node (ref "RN1") (pin "3") (pinfunction "3_3") (pintype "passive"))
      (node (ref "X1") (pin "2") (pinfunction "S_2") (pintype "passive"))
    )
    (net (code "77") (name "Net-(IC9A-C)") (class "Default")
      (node (ref "IC9") (pin "13") (pinfunction "C_13") (pintype "input"))
      (node (ref "RN1") (pin "4") (pinfunction "4_4") (pintype "passive"))
      (node (ref "X1") (pin "3") (pinfunction "S_3") (pintype "passive"))
    )
    (net (code "78") (name "Net-(IC9A-D)") (class "Default")
      (node (ref "IC9") (pin "14") (pinfunction "D_14") (pintype "input"))
      (node (ref "RN1") (pin "5") (pinfunction "5_5") (pintype "passive"))
      (node (ref "X1") (pin "4") (pinfunction "S_4") (pintype "passive"))
    )
    (net (code "79") (name "Net-(IC9A-E)") (class "Default")
      (node (ref "IC9") (pin "3") (pinfunction "E_3") (pintype "input"))
      (node (ref "RN1") (pin "6") (pinfunction "6_6") (pintype "passive"))
      (node (ref "X1") (pin "5") (pinfunction "S_5") (pintype "passive"))
    )
    (net (code "80") (name "Net-(IC9A-F)") (class "Default")
      (node (ref "IC9") (pin "4") (pinfunction "F_4") (pintype "input"))
      (node (ref "RN1") (pin "7") (pinfunction "7_7") (pintype "passive"))
      (node (ref "X1") (pin "6") (pinfunction "S_6") (pintype "passive"))
    )
    (net (code "81") (name "Net-(IC9A-G)") (class "Default")
      (node (ref "IC9") (pin "5") (pinfunction "G_5") (pintype "input"))
      (node (ref "RN1") (pin "8") (pinfunction "8_8") (pintype "passive"))
      (node (ref "X1") (pin "7") (pinfunction "S_7") (pintype "passive"))
    )
    (net (code "82") (name "Net-(IC9A-H)") (class "Default")
      (node (ref "IC9") (pin "6") (pinfunction "H_6") (pintype "input"))
      (node (ref "RN1") (pin "9") (pinfunction "9_9") (pintype "passive"))
      (node (ref "X1") (pin "8") (pinfunction "S_8") (pintype "passive"))
    )
    (net (code "83") (name "VCC") (class "Default")
      (node (ref "C10") (pin "2") (pinfunction "2_2") (pintype "passive"))
      (node (ref "C11") (pin "2") (pinfunction "2_2") (pintype "passive"))
      (node (ref "C12") (pin "2") (pinfunction "2_2") (pintype "passive"))
      (node (ref "C13") (pin "2") (pinfunction "2_2") (pintype "passive"))
      (node (ref "C14") (pin "2") (pinfunction "2_2") (pintype "passive"))
      (node (ref "C3") (pin "2") (pinfunction "2_2") (pintype "passive"))
      (node (ref "C4") (pin "1") (pinfunction "+_1") (pintype "passive"))
      (node (ref "C6") (pin "2") (pinfunction "2_2") (pintype "passive"))
      (node (ref "C7") (pin "2") (pinfunction "2_2") (pintype "passive"))
      (node (ref "C8") (pin "2") (pinfunction "2_2") (pintype "passive"))
      (node (ref "C9") (pin "2") (pinfunction "2_2") (pintype "passive"))
      (node (ref "IC1") (pin "20") (pinfunction "VCC/ANALOG_20") (pintype "passive"))
      (node (ref "IC1") (pin "21") (pinfunction "ANALOG_REFERENCE_21") (pintype "passive"))
      (node (ref "IC1") (pin "7") (pinfunction "VCC_7") (pintype "power_in"))
      (node (ref "ICSP") (pin "2") (pinfunction "2_2") (pintype "passive"))
      (node (ref "J1") (pin "PWR") (pinfunction "PWR_PWR") (pintype "bidirectional"))
      (node (ref "R1") (pin "P$2") (pinfunction "2_P$2") (pintype "passive"))
      (node (ref "RN1") (pin "1") (pinfunction "1_1") (pintype "passive"))
      (node (ref "RN2") (pin "1") (pinfunction "1_1") (pintype "passive"))
      (node (ref "RN3") (pin "1") (pinfunction "1_1") (pintype "passive"))
      (node (ref "RN4") (pin "1") (pinfunction "1_1") (pintype "passive"))
      (node (ref "RN5") (pin "1") (pinfunction "1_1") (pintype "passive"))
      (node (ref "RN6") (pin "1") (pinfunction "1_1") (pintype "passive"))
      (node (ref "RN7") (pin "1") (pinfunction "1_1") (pintype "passive"))
      (node (ref "SERIAL_PROG") (pin "4") (pinfunction "4_4") (pintype "passive"))
    )
    (net (code "84") (name "unconnected-(IC1-ANALOG_0-Pad23)") (class "Default")
      (node (ref "IC1") (pin "23") (pinfunction "ANALOG_0_23") (pintype "bidirectional"))
    )
    (net (code "85") (name "unconnected-(IC1-ANALOG_1-Pad24)") (class "Default")
      (node (ref "IC1") (pin "24") (pinfunction "ANALOG_1_24") (pintype "bidirectional"))
    )
    (net (code "86") (name "unconnected-(IC1-ANALOG_2-Pad25)") (class "Default")
      (node (ref "IC1") (pin "25") (pinfunction "ANALOG_2_25") (pintype "bidirectional"))
    )
    (net (code "87") (name "unconnected-(IC1-ANALOG_3-Pad26)") (class "Default")
      (node (ref "IC1") (pin "26") (pinfunction "ANALOG_3_26") (pintype "bidirectional"))
    )
    (net (code "88") (name "unconnected-(IC1-ANALOG_4-Pad27)") (class "Default")
      (node (ref "IC1") (pin "27") (pinfunction "ANALOG_4_27") (pintype "bidirectional"))
    )
    (net (code "89") (name "unconnected-(IC1-ANALOG_5-Pad28)") (class "Default")
      (node (ref "IC1") (pin "28") (pinfunction "ANALOG_5_28") (pintype "bidirectional"))
    )
    (net (code "90") (name "unconnected-(IC1-DIGITAL_2-Pad4)") (class "Default")
      (node (ref "IC1") (pin "4") (pinfunction "DIGITAL_2_4") (pintype "bidirectional"))
    )
    (net (code "91") (name "unconnected-(IC1-DIGITAL_3(PWM)-Pad5)") (class "Default")
      (node (ref "IC1") (pin "5") (pinfunction "DIGITAL_3(PWM)_5") (pintype "bidirectional"))
    )
    (net (code "92") (name "unconnected-(IC1-DIGITAL_4-Pad6)") (class "Default")
      (node (ref "IC1") (pin "6") (pinfunction "DIGITAL_4_6") (pintype "bidirectional"))
    )
    (net (code "93") (name "unconnected-(IC1-DIGITAL_5(PWM)-Pad11)") (class "Default")
      (node (ref "IC1") (pin "11") (pinfunction "DIGITAL_5(PWM)_11") (pintype "bidirectional"))
    )
    (net (code "94") (name "unconnected-(IC1-DIGITAL_6(PWM)-Pad12)") (class "Default")
      (node (ref "IC1") (pin "12") (pinfunction "DIGITAL_6(PWM)_12") (pintype "bidirectional"))
    )
    (net (code "95") (name "unconnected-(IC1-DIGITAL_7-Pad13)") (class "Default")
      (node (ref "IC1") (pin "13") (pinfunction "DIGITAL_7_13") (pintype "bidirectional"))
    )
    (net (code "96") (name "unconnected-(IC1-DIGITAL_8-Pad14)") (class "Default")
      (node (ref "IC1") (pin "14") (pinfunction "DIGITAL_8_14") (pintype "bidirectional"))
    )
    (net (code "97") (name "unconnected-(IC1-DIGITAL_9(PWM)-Pad15)") (class "Default")
      (node (ref "IC1") (pin "15") (pinfunction "DIGITAL_9(PWM)_15") (pintype "bidirectional"))
    )
    (net (code "98") (name "unconnected-(IC2A-~{QH}-Pad7)") (class "Default")
      (node (ref "IC2") (pin "7") (pinfunction "~{QH}_7") (pintype "output"))
    )
    (net (code "99") (name "unconnected-(IC3A-~{QH}-Pad7)") (class "Default")
      (node (ref "IC3") (pin "7") (pinfunction "~{QH}_7") (pintype "output"))
    )
    (net (code "100") (name "unconnected-(IC4A-~{QH}-Pad7)") (class "Default")
      (node (ref "IC4") (pin "7") (pinfunction "~{QH}_7") (pintype "output"))
    )
    (net (code "101") (name "unconnected-(IC5A-~{QH}-Pad7)") (class "Default")
      (node (ref "IC5") (pin "7") (pinfunction "~{QH}_7") (pintype "output"))
    )
    (net (code "102") (name "unconnected-(IC6A-~{QH}-Pad7)") (class "Default")
      (node (ref "IC6") (pin "7") (pinfunction "~{QH}_7") (pintype "output"))
    )
    (net (code "103") (name "unconnected-(IC7A-QH-Pad9)") (class "Default")
      (node (ref "IC7") (pin "9") (pinfunction "QH_9") (pintype "output"))
    )
    (net (code "104") (name "unconnected-(IC8A-~{QH}-Pad7)") (class "Default")
      (node (ref "IC8") (pin "7") (pinfunction "~{QH}_7") (pintype "output"))
    )
    (net (code "105") (name "unconnected-(IC9A-~{QH}-Pad7)") (class "Default")
      (node (ref "IC9") (pin "7") (pinfunction "~{QH}_7") (pintype "output"))
    )
    (net (code "106") (name "unconnected-(RN7-Pad6)") (class "Default")
      (node (ref "RN7") (pin "6") (pinfunction "6_6") (pintype "passive"))
    )
    (net (code "107") (name "unconnected-(RN7-Pad7)") (class "Default")
      (node (ref "RN7") (pin "7") (pinfunction "7_7") (pintype "passive"))
    )
    (net (code "108") (name "unconnected-(RN7-Pad8)") (class "Default")
      (node (ref "RN7") (pin "8") (pinfunction "8_8") (pintype "passive"))
    )
    (net (code "109") (name "unconnected-(RN7-Pad9)") (class "Default")
      (node (ref "RN7") (pin "9") (pinfunction "9_9") (pintype "passive"))
    )
    (net (code "110") (name "unconnected-(RN7-Pad10)") (class "Default")
      (node (ref "RN7") (pin "10") (pinfunction "10_10") (pintype "passive"))
    )
    (net (code "111") (name "unconnected-(RN7-Pad11)") (class "Default")
      (node (ref "RN7") (pin "11") (pinfunction "11_11") (pintype "passive"))
    )
    (net (code "112") (name "unconnected-(SERIAL_PROG-Pad5)") (class "Default")
      (node (ref "SERIAL_PROG") (pin "5") (pinfunction "5_5") (pintype "passive"))
    )
    (net (code "113") (name "unconnected-(X7B-S-Pad10)") (class "Default")
      (node (ref "X7") (pin "10") (pinfunction "S_10") (pintype "passive"))
    )
    (net (code "114") (name "unconnected-(X7F-S-Pad5)") (class "Default")
      (node (ref "X7") (pin "5") (pinfunction "S_5") (pintype "passive"))
    )
    (net (code "115") (name "unconnected-(X7G-S-Pad6)") (class "Default")
      (node (ref "X7") (pin "6") (pinfunction "S_6") (pintype "passive"))
    )
    (net (code "116") (name "unconnected-(X7H-S-Pad7)") (class "Default")
      (node (ref "X7") (pin "7") (pinfunction "S_7") (pintype "passive"))
    )
    (net (code "117") (name "unconnected-(X7I-S-Pad8)") (class "Default")
      (node (ref "X7") (pin "8") (pinfunction "S_8") (pintype "passive"))
    )
    (net (code "118") (name "unconnected-(X7J-S-Pad9)") (class "Default")
      (node (ref "X7") (pin "9") (pinfunction "S_9") (pintype "passive"))
    )
  )
)
